# robot_sumo_easyeda.net
KiCad netlist of a schematic drawn in EasyEDA
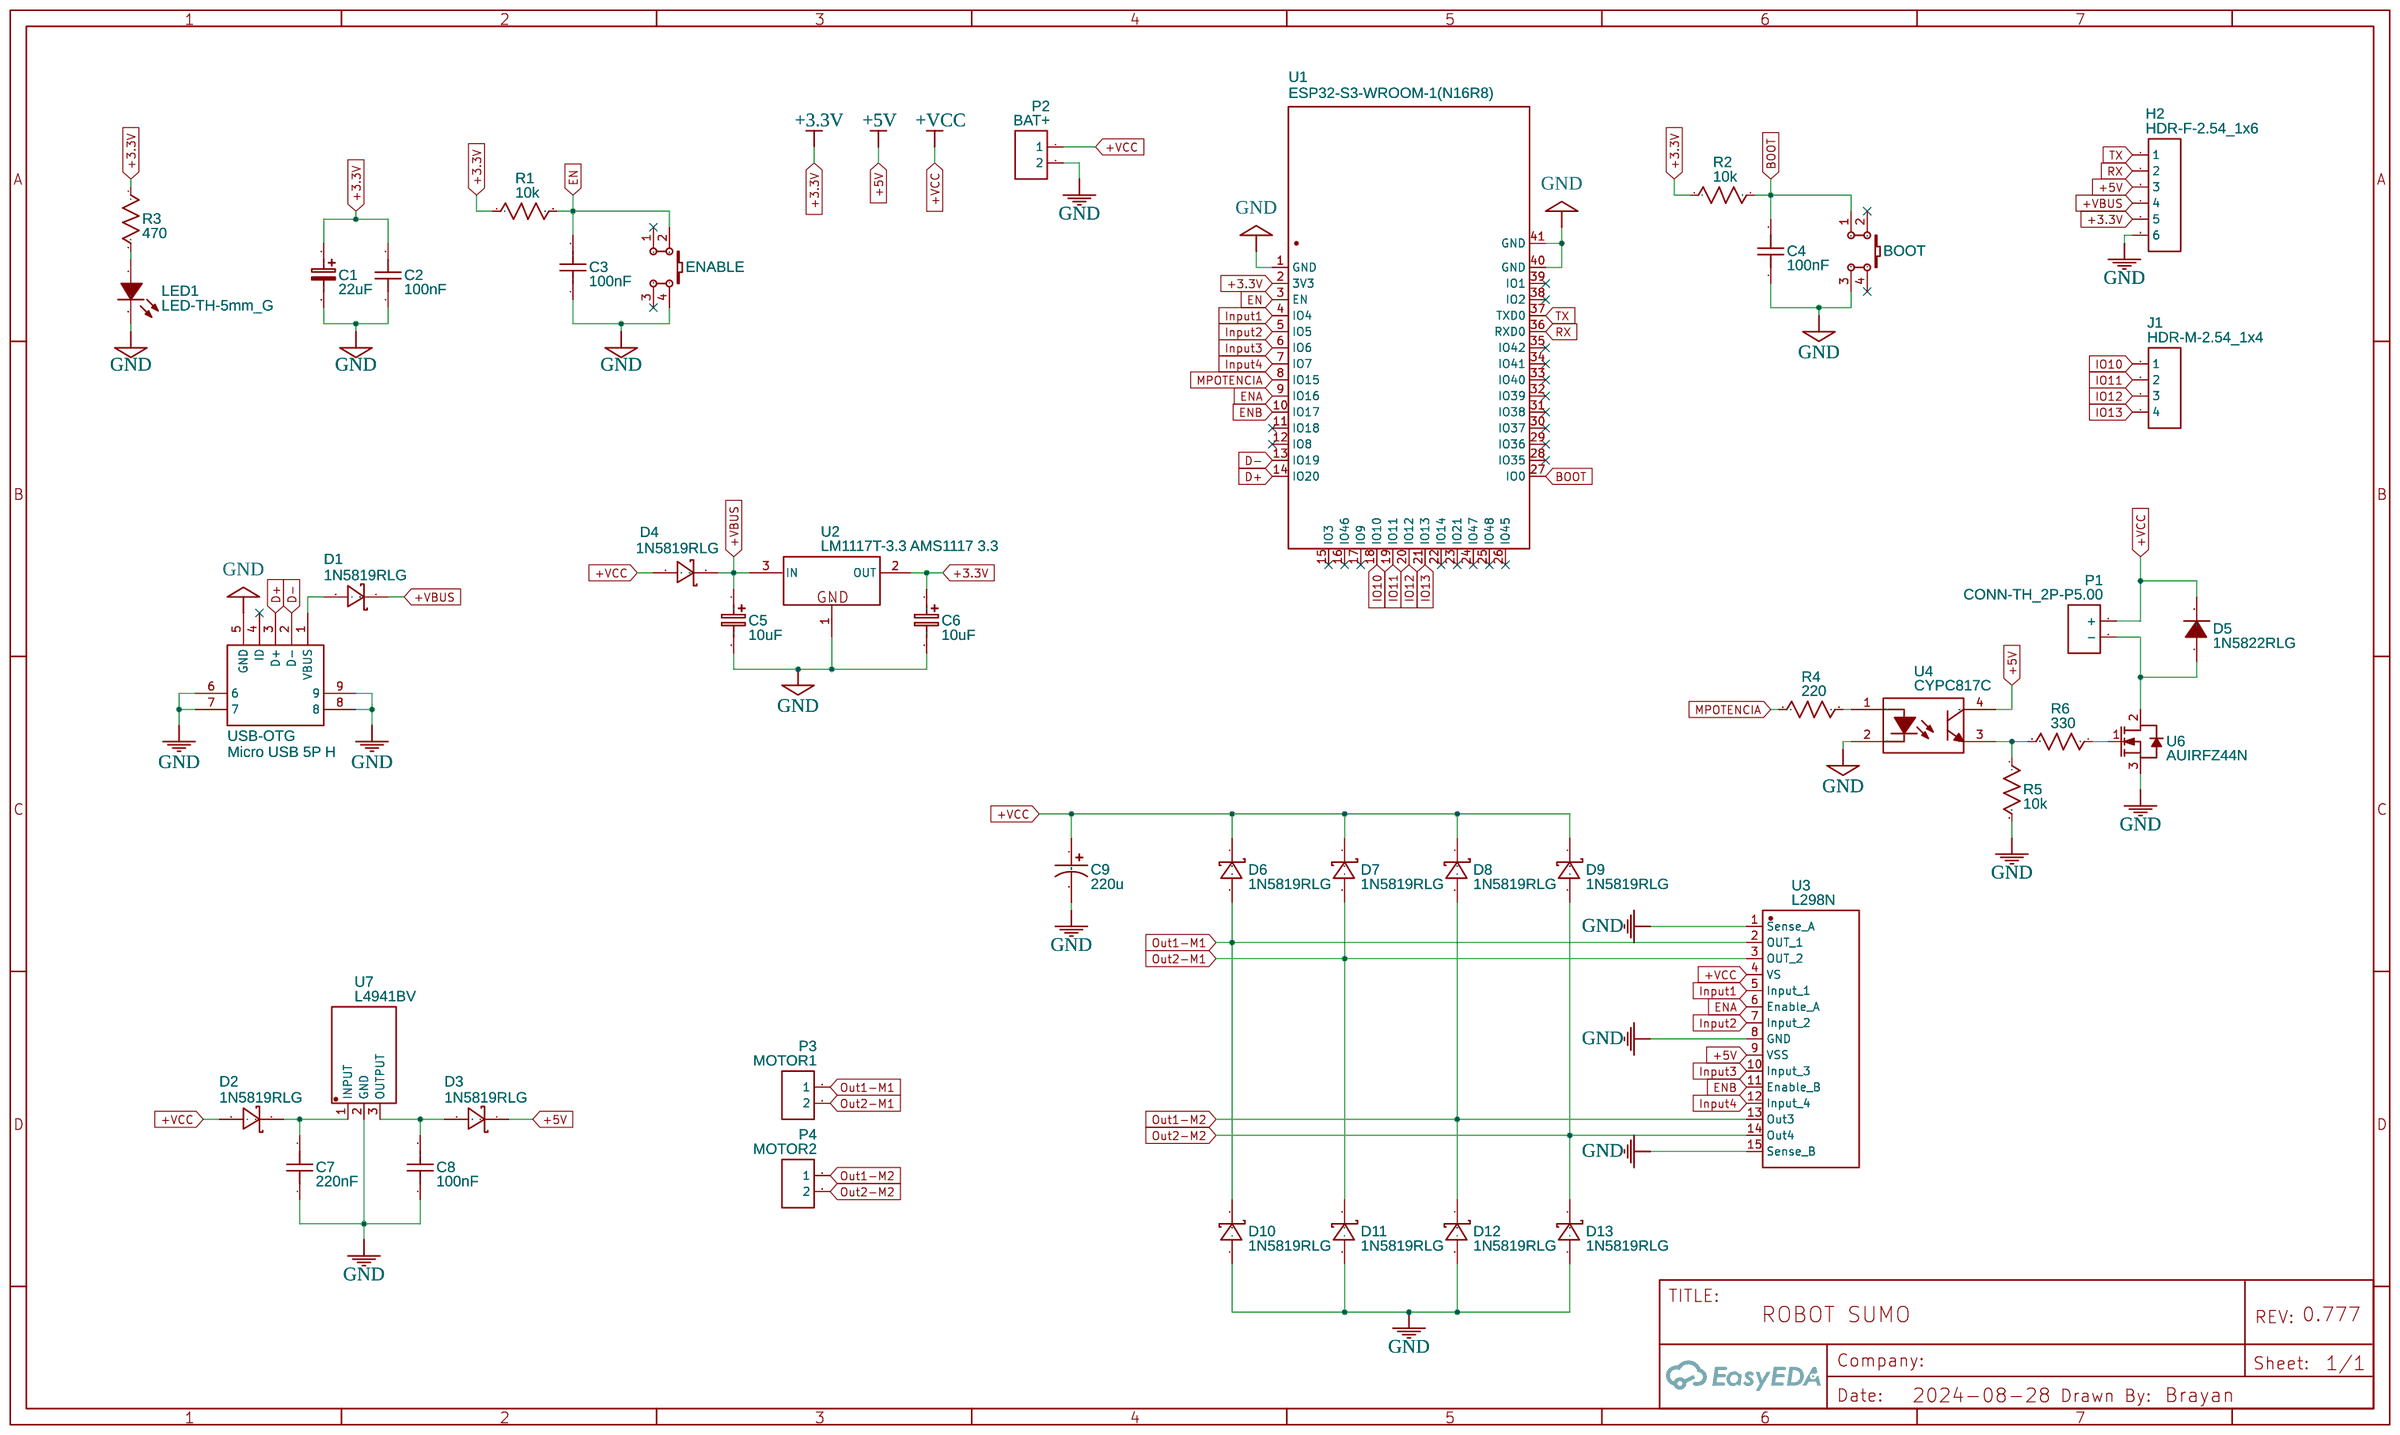
[diagram p0: schematic sheet]

(export (version "E")
  (design (tool "Eeschema 10.0.6"))
  (components
    (comp (ref "BOOT")
      (value "K4-6×6_TH")
      (fields (field (name "Manufacturer Part") "K2-1102DP-E4SW-04") (field (name "Manufacturer") "韩国韩荣"))
      (libsource (lib "") (part "K4-6×6_TH_1"))
    )
    (comp (ref "C1") (value "22uF") (libsource (lib "") (part "CE_TH_D5.0×F2.0_EU_2")))
    (comp (ref "C2")
      (value "100nF")
      (fields
        (field (name "Manufacturer Part") "CC1E104ZA1FD3F5O10MF")
        (field (name "Manufacturer") "Dersonic(德尔创)")
      )
      (libsource (lib "") (part "CC1E104ZA1FD3F5O10MF"))
    )
    (comp (ref "C3")
      (value "100nF")
      (fields
        (field (name "Manufacturer Part") "CC1E104ZA1FD3F5O10MF")
        (field (name "Manufacturer") "Dersonic(德尔创)")
      )
      (libsource (lib "") (part "CC1E104ZA1FD3F5O10MF"))
    )
    (comp (ref "C4")
      (value "100nF")
      (fields
        (field (name "Manufacturer Part") "CC1E104ZA1FD3F5O10MF")
        (field (name "Manufacturer") "Dersonic(德尔创)")
      )
      (libsource (lib "") (part "CC1E104ZA1FD3F5O10MF"))
    )
    (comp (ref "C5") (value "10uF") (libsource (lib "") (part "CE_TH_D5.0×F2.0_EU_1")))
    (comp (ref "C6") (value "10uF") (libsource (lib "") (part "CE_TH_D5.0×F2.0_EU")))
    (comp (ref "C7")
      (value "220nF")
      (fields
        (field (name "Manufacturer Part") "CC1E104ZA1FD3F5O10MF")
        (field (name "Manufacturer") "Dersonic(德尔创)")
      )
      (libsource (lib "") (part "CC1E104ZA1FD3F5O10MF"))
    )
    (comp (ref "C8")
      (value "100nF")
      (fields
        (field (name "Manufacturer Part") "CC1E104ZA1FD3F5O10MF")
        (field (name "Manufacturer") "Dersonic(德尔创)")
      )
      (libsource (lib "") (part "CC1E104ZA1FD3F5O10MF"))
    )
    (comp (ref "C9") (value "220u") (libsource (lib "") (part "CE_TH_D8.0×F3.5_US")))
    (comp (ref "D1")
      (value "1N5819RLG")
      (fields (field (name "Manufacturer") "onsemi(安森美)"))
      (libsource (lib "") (part "1N5819RLG_1"))
    )
    (comp (ref "D2")
      (value "1N5819RLG")
      (fields (field (name "Manufacturer") "onsemi(安森美)"))
      (libsource (lib "") (part "1N5819RLG_1"))
    )
    (comp (ref "D3")
      (value "1N5819RLG")
      (fields (field (name "Manufacturer") "onsemi(安森美)"))
      (libsource (lib "") (part "1N5819RLG_1"))
    )
    (comp (ref "D4")
      (value "1N5819RLG")
      (fields (field (name "Manufacturer") "onsemi(安森美)"))
      (libsource (lib "") (part "1N5819RLG_1"))
    )
    (comp (ref "D5")
      (value "1N5822RLG")
      (fields (field (name "Manufacturer") "onsemi(安森美)"))
      (libsource (lib "") (part "1N5822RLG"))
    )
    (comp (ref "D6")
      (value "1N5819RLG")
      (fields (field (name "Manufacturer") "onsemi(安森美)"))
      (libsource (lib "") (part "1N5819RLG"))
    )
    (comp (ref "D7")
      (value "1N5819RLG")
      (fields (field (name "Manufacturer") "onsemi(安森美)"))
      (libsource (lib "") (part "1N5819RLG"))
    )
    (comp (ref "D8")
      (value "1N5819RLG")
      (fields (field (name "Manufacturer") "onsemi(安森美)"))
      (libsource (lib "") (part "1N5819RLG"))
    )
    (comp (ref "D9")
      (value "1N5819RLG")
      (fields (field (name "Manufacturer") "onsemi(安森美)"))
      (libsource (lib "") (part "1N5819RLG"))
    )
    (comp (ref "D10")
      (value "1N5819RLG")
      (fields (field (name "Manufacturer") "onsemi(安森美)"))
      (libsource (lib "") (part "1N5819RLG"))
    )
    (comp (ref "D11")
      (value "1N5819RLG")
      (fields (field (name "Manufacturer") "onsemi(安森美)"))
      (libsource (lib "") (part "1N5819RLG"))
    )
    (comp (ref "D12")
      (value "1N5819RLG")
      (fields (field (name "Manufacturer") "onsemi(安森美)"))
      (libsource (lib "") (part "1N5819RLG"))
    )
    (comp (ref "D13")
      (value "1N5819RLG")
      (fields (field (name "Manufacturer") "onsemi(安森美)"))
      (libsource (lib "") (part "1N5819RLG"))
    )
    (comp (ref "ENABLE")
      (value "K4-6×6_TH")
      (fields (field (name "Manufacturer Part") "K2-1102DP-E4SW-04") (field (name "Manufacturer") "韩国韩荣"))
      (libsource (lib "") (part "K4-6×6_TH"))
    )
    (comp (ref "H2") (value "HDR-F-2.54_1x6") (libsource (lib "") (part "HDR-F-2.54_1x6")))
    (comp (ref "J1") (value "HDR-M-2.54_1x4") (libsource (lib "") (part "HDR-M-2.54_1x4")))
    (comp (ref "LED1")
      (value "LED-TH-5mm_G")
      (fields
        (field (name "Manufacturer Part") "333-2SYGD/S530-E2")
        (field (name "Manufacturer") "EVERLIGHT(台湾亿光)")
      )
      (libsource (lib "") (part "LED-TH-5mm_G"))
    )
    (comp (ref "P1") (value "CONN-TH_2P-P5.00") (libsource (lib "") (part "CONN-TH_2P-P5.00_1")))
    (comp (ref "P2") (value "BAT+") (libsource (lib "") (part "CONN-TH_2P-P5.00")))
    (comp (ref "P3") (value "MOTOR1") (libsource (lib "") (part "CONN-TH_2P-P5.00")))
    (comp (ref "P4") (value "MOTOR2") (libsource (lib "") (part "CONN-TH_2P-P5.00")))
    (comp (ref "R1") (value "10k") (libsource (lib "") (part "R_AXIAL-0.4_US")))
    (comp (ref "R2") (value "10k") (libsource (lib "") (part "R_AXIAL-0.4_US")))
    (comp (ref "R3") (value "470") (libsource (lib "") (part "R_AXIAL-0.4_US_2")))
    (comp (ref "R4") (value "220") (libsource (lib "") (part "R_AXIAL-0.4_US_1")))
    (comp (ref "R5") (value "10k") (libsource (lib "") (part "R_AXIAL-0.4_US_2")))
    (comp (ref "R6") (value "330") (libsource (lib "") (part "R_AXIAL-0.4_US_1")))
    (comp (ref "U1")
      (value "ESP32-S3-WROOM-1(N16R8)")
      (fields
        (field (name "Manufacturer Part") "ESP32-S3-WROOM-1-N16R8")
        (field (name "Manufacturer") "ESPRESSIF(乐鑫)")
      )
      (libsource (lib "") (part "ESP32-S3-WROOM-1(N16R8)"))
    )
    (comp (ref "U2")
      (value "LM1117T-3.3 AMS1117 3.3")
      (fields (field (name "Manufacturer Part") "LM1117T-3.3") (field (name "Manufacturer") "HGSEMI(华冠)"))
      (libsource (lib "") (part "LM1117T-3.3"))
    )
    (comp (ref "U3")
      (value "L298N")
      (fields (field (name "Manufacturer") "HGSEMI(华冠)"))
      (libsource (lib "") (part "L298N"))
    )
    (comp (ref "U4")
      (value "CYPC817C")
      (fields (field (name "Manufacturer") "OCIC(卓睿科)"))
      (libsource (lib "") (part "CYPC817C"))
    )
    (comp (ref "U6")
      (value "AUIRFZ44N")
      (fields (field (name "Manufacturer") "Infineon(英飞凌)"))
      (libsource (lib "") (part "AUIRFZ44N"))
    )
    (comp (ref "U7")
      (value "L4941BV")
      (fields (field (name "Manufacturer") "ST(意法半导体)"))
      (libsource (lib "") (part "L4941BV"))
    )
    (comp (ref "USB-OTG")
      (value "Micro USB 5P H")
      (fields (field (name "Manufacturer Part") "920-E52A2021S10101") (field (name "Manufacturer") "精拓金"))
      (libsource (lib "") (part "Micro USB 5P H"))
    )
  )
  (nets
    (net (code "1") (name "+3.3V") (class "Default")
      (node (ref "C1") (pin "1") (pinfunction "1_1") (pintype "unspecified"))
      (node (ref "C2") (pin "2") (pinfunction "2_2") (pintype "unspecified"))
      (node (ref "C6") (pin "1") (pinfunction "1_1") (pintype "unspecified"))
      (node (ref "H2") (pin "5") (pinfunction "5_5") (pintype "input"))
      (node (ref "R1") (pin "1") (pinfunction "1_1") (pintype "unspecified"))
      (node (ref "R2") (pin "1") (pinfunction "1_1") (pintype "unspecified"))
      (node (ref "R3") (pin "1") (pinfunction "1_1") (pintype "unspecified"))
      (node (ref "U1") (pin "2") (pinfunction "3V3_2") (pintype "unspecified"))
      (node (ref "U2") (pin "2") (pinfunction "OUT_2") (pintype "unspecified"))
    )
    (net (code "2") (name "+5V") (class "Default")
      (node (ref "D3") (pin "1") (pinfunction "C_1") (pintype "unspecified"))
      (node (ref "H2") (pin "3") (pinfunction "3_3") (pintype "input"))
      (node (ref "U3") (pin "9") (pinfunction "VSS_9") (pintype "unspecified"))
      (node (ref "U4") (pin "4") (pinfunction "COL_4") (pintype "unspecified"))
    )
    (net (code "3") (name "+VBUS") (class "Default")
      (node (ref "C5") (pin "1") (pinfunction "1_1") (pintype "unspecified"))
      (node (ref "D1") (pin "1") (pinfunction "C_1") (pintype "unspecified"))
      (node (ref "D4") (pin "1") (pinfunction "C_1") (pintype "unspecified"))
      (node (ref "H2") (pin "4") (pinfunction "4_4") (pintype "input"))
      (node (ref "U2") (pin "3") (pinfunction "IN_3") (pintype "unspecified"))
    )
    (net (code "4") (name "+VCC") (class "Default")
      (node (ref "C9") (pin "1") (pinfunction "1_1") (pintype "unspecified"))
      (node (ref "D2") (pin "2") (pinfunction "A_2") (pintype "unspecified"))
      (node (ref "D4") (pin "2") (pinfunction "A_2") (pintype "unspecified"))
      (node (ref "D5") (pin "1") (pinfunction "C_1") (pintype "unspecified"))
      (node (ref "D6") (pin "1") (pinfunction "C_1") (pintype "unspecified"))
      (node (ref "D7") (pin "1") (pinfunction "C_1") (pintype "unspecified"))
      (node (ref "D8") (pin "1") (pinfunction "C_1") (pintype "unspecified"))
      (node (ref "D9") (pin "1") (pinfunction "C_1") (pintype "unspecified"))
      (node (ref "P1") (pin "1") (pinfunction "+_1") (pintype "unspecified"))
      (node (ref "P2") (pin "1") (pinfunction "1_1") (pintype "unspecified"))
      (node (ref "U3") (pin "4") (pinfunction "VS_4") (pintype "unspecified"))
    )
    (net (code "5") (name "BOOT") (class "Default")
      (node (ref "BOOT") (pin "1") (pinfunction "1_1") (pintype "unspecified"))
      (node (ref "C4") (pin "2") (pinfunction "2_2") (pintype "unspecified"))
      (node (ref "R2") (pin "2") (pinfunction "2_2") (pintype "unspecified"))
      (node (ref "U1") (pin "27") (pinfunction "IO0_27") (pintype "unspecified"))
    )
    (net (code "6") (name "D+") (class "Default")
      (node (ref "U1") (pin "14") (pinfunction "IO20_14") (pintype "unspecified"))
      (node (ref "USB-OTG") (pin "3") (pinfunction "D+_3") (pintype "unspecified"))
    )
    (net (code "7") (name "D-") (class "Default")
      (node (ref "U1") (pin "13") (pinfunction "IO19_13") (pintype "unspecified"))
      (node (ref "USB-OTG") (pin "2") (pinfunction "D-_2") (pintype "unspecified"))
    )
    (net (code "8") (name "EN") (class "Default")
      (node (ref "C3") (pin "2") (pinfunction "2_2") (pintype "unspecified"))
      (node (ref "ENABLE") (pin "2") (pinfunction "2_2") (pintype "unspecified"))
      (node (ref "R1") (pin "2") (pinfunction "2_2") (pintype "unspecified"))
      (node (ref "U1") (pin "3") (pinfunction "EN_3") (pintype "unspecified"))
    )
    (net (code "9") (name "ENA") (class "Default")
      (node (ref "U1") (pin "9") (pinfunction "IO16_9") (pintype "unspecified"))
      (node (ref "U3") (pin "6") (pinfunction "Enable_A_6") (pintype "unspecified"))
    )
    (net (code "10") (name "ENB") (class "Default")
      (node (ref "U1") (pin "10") (pinfunction "IO17_10") (pintype "unspecified"))
      (node (ref "U3") (pin "11") (pinfunction "Enable_B_11") (pintype "unspecified"))
    )
    (net (code "11") (name "GND") (class "Default")
      (node (ref "BOOT") (pin "3") (pinfunction "3_3") (pintype "unspecified"))
      (node (ref "C1") (pin "2") (pinfunction "2_2") (pintype "unspecified"))
      (node (ref "C2") (pin "1") (pinfunction "1_1") (pintype "unspecified"))
      (node (ref "C3") (pin "1") (pinfunction "1_1") (pintype "unspecified"))
      (node (ref "C4") (pin "1") (pinfunction "1_1") (pintype "unspecified"))
      (node (ref "C5") (pin "2") (pinfunction "2_2") (pintype "unspecified"))
      (node (ref "C6") (pin "2") (pinfunction "2_2") (pintype "unspecified"))
      (node (ref "C7") (pin "1") (pinfunction "1_1") (pintype "unspecified"))
      (node (ref "C8") (pin "1") (pinfunction "1_1") (pintype "unspecified"))
      (node (ref "C9") (pin "2") (pinfunction "2_2") (pintype "unspecified"))
      (node (ref "D10") (pin "2") (pinfunction "A_2") (pintype "unspecified"))
      (node (ref "D11") (pin "2") (pinfunction "A_2") (pintype "unspecified"))
      (node (ref "D12") (pin "2") (pinfunction "A_2") (pintype "unspecified"))
      (node (ref "D13") (pin "2") (pinfunction "A_2") (pintype "unspecified"))
      (node (ref "ENABLE") (pin "4") (pinfunction "4_4") (pintype "unspecified"))
      (node (ref "H2") (pin "6") (pinfunction "6_6") (pintype "input"))
      (node (ref "LED1") (pin "2") (pinfunction "2_2") (pintype "unspecified"))
      (node (ref "P2") (pin "2") (pinfunction "2_2") (pintype "unspecified"))
      (node (ref "R5") (pin "2") (pinfunction "2_2") (pintype "unspecified"))
      (node (ref "U1") (pin "1") (pinfunction "GND_1") (pintype "unspecified"))
      (node (ref "U1") (pin "40") (pinfunction "GND_40") (pintype "unspecified"))
      (node (ref "U1") (pin "41") (pinfunction "GND_41") (pintype "unspecified"))
      (node (ref "U2") (pin "1") (pinfunction "GND_1") (pintype "unspecified"))
      (node (ref "U3") (pin "1") (pinfunction "Sense_A_1") (pintype "unspecified"))
      (node (ref "U3") (pin "15") (pinfunction "Sense_B_15") (pintype "unspecified"))
      (node (ref "U3") (pin "8") (pinfunction "GND_8") (pintype "unspecified"))
      (node (ref "U4") (pin "2") (pinfunction "CAT_2") (pintype "unspecified"))
      (node (ref "U6") (pin "3") (pinfunction "S_3") (pintype "unspecified"))
      (node (ref "U7") (pin "2") (pinfunction "GND_2") (pintype "unspecified"))
      (node (ref "USB-OTG") (pin "5") (pinfunction "GND_5") (pintype "unspecified"))
      (node (ref "USB-OTG") (pin "6") (pinfunction "6_6") (pintype "unspecified"))
      (node (ref "USB-OTG") (pin "7") (pinfunction "7_7") (pintype "unspecified"))
      (node (ref "USB-OTG") (pin "8") (pinfunction "8_8") (pintype "unspecified"))
      (node (ref "USB-OTG") (pin "9") (pinfunction "9_9") (pintype "unspecified"))
    )
    (net (code "12") (name "IO10") (class "Default")
      (node (ref "J1") (pin "1") (pinfunction "1_1") (pintype "unspecified"))
      (node (ref "U1") (pin "18") (pinfunction "IO10_18") (pintype "unspecified"))
    )
    (net (code "13") (name "IO11") (class "Default")
      (node (ref "J1") (pin "2") (pinfunction "2_2") (pintype "unspecified"))
      (node (ref "U1") (pin "19") (pinfunction "IO11_19") (pintype "unspecified"))
    )
    (net (code "14") (name "IO12") (class "Default")
      (node (ref "J1") (pin "3") (pinfunction "3_3") (pintype "unspecified"))
      (node (ref "U1") (pin "20") (pinfunction "IO12_20") (pintype "unspecified"))
    )
    (net (code "15") (name "IO13") (class "Default")
      (node (ref "J1") (pin "4") (pinfunction "4_4") (pintype "unspecified"))
      (node (ref "U1") (pin "21") (pinfunction "IO13_21") (pintype "unspecified"))
    )
    (net (code "16") (name "Input1") (class "Default")
      (node (ref "U1") (pin "4") (pinfunction "IO4_4") (pintype "unspecified"))
      (node (ref "U3") (pin "5") (pinfunction "Input_1_5") (pintype "unspecified"))
    )
    (net (code "17") (name "Input2") (class "Default")
      (node (ref "U1") (pin "5") (pinfunction "IO5_5") (pintype "unspecified"))
      (node (ref "U3") (pin "7") (pinfunction "Input_2_7") (pintype "unspecified"))
    )
    (net (code "18") (name "Input3") (class "Default")
      (node (ref "U1") (pin "6") (pinfunction "IO6_6") (pintype "unspecified"))
      (node (ref "U3") (pin "10") (pinfunction "Input_3_10") (pintype "unspecified"))
    )
    (net (code "19") (name "Input4") (class "Default")
      (node (ref "U1") (pin "7") (pinfunction "IO7_7") (pintype "unspecified"))
      (node (ref "U3") (pin "12") (pinfunction "Input_4_12") (pintype "unspecified"))
    )
    (net (code "20") (name "MPOTENCIA") (class "Default")
      (node (ref "R4") (pin "2") (pinfunction "2_2") (pintype "unspecified"))
      (node (ref "U1") (pin "8") (pinfunction "IO15_8") (pintype "unspecified"))
    )
    (net (code "21") (name "Net-(D1-A)") (class "Default")
      (node (ref "D1") (pin "2") (pinfunction "A_2") (pintype "unspecified"))
      (node (ref "USB-OTG") (pin "1") (pinfunction "VBUS_1") (pintype "unspecified"))
    )
    (net (code "22") (name "Net-(D2-C)") (class "Default")
      (node (ref "C7") (pin "2") (pinfunction "2_2") (pintype "unspecified"))
      (node (ref "D2") (pin "1") (pinfunction "C_1") (pintype "unspecified"))
      (node (ref "U7") (pin "1") (pinfunction "INPUT_1") (pintype "unspecified"))
    )
    (net (code "23") (name "Net-(D3-A)") (class "Default")
      (node (ref "C8") (pin "2") (pinfunction "2_2") (pintype "unspecified"))
      (node (ref "D3") (pin "2") (pinfunction "A_2") (pintype "unspecified"))
      (node (ref "U7") (pin "3") (pinfunction "OUTPUT_3") (pintype "unspecified"))
    )
    (net (code "24") (name "Net-(D5-A)") (class "Default")
      (node (ref "D5") (pin "2") (pinfunction "A_2") (pintype "unspecified"))
      (node (ref "P1") (pin "2") (pinfunction "-_2") (pintype "unspecified"))
      (node (ref "U6") (pin "2") (pinfunction "D_2") (pintype "unspecified"))
    )
    (net (code "25") (name "Net-(LED1-Pad1)") (class "Default")
      (node (ref "LED1") (pin "1") (pinfunction "1_1") (pintype "unspecified"))
      (node (ref "R3") (pin "2") (pinfunction "2_2") (pintype "unspecified"))
    )
    (net (code "26") (name "Net-(U4-AN)") (class "Default")
      (node (ref "R4") (pin "1") (pinfunction "1_1") (pintype "unspecified"))
      (node (ref "U4") (pin "1") (pinfunction "AN_1") (pintype "unspecified"))
    )
    (net (code "27") (name "Net-(U4-EMI)") (class "Default")
      (node (ref "R5") (pin "1") (pinfunction "1_1") (pintype "unspecified"))
      (node (ref "R6") (pin "2") (pinfunction "2_2") (pintype "unspecified"))
      (node (ref "U4") (pin "3") (pinfunction "EMI_3") (pintype "unspecified"))
    )
    (net (code "28") (name "Net-(U6-G)") (class "Default")
      (node (ref "R6") (pin "1") (pinfunction "1_1") (pintype "unspecified"))
      (node (ref "U6") (pin "1") (pinfunction "G_1") (pintype "unspecified"))
    )
    (net (code "29") (name "Out1-M1") (class "Default")
      (node (ref "D10") (pin "1") (pinfunction "C_1") (pintype "unspecified"))
      (node (ref "D6") (pin "2") (pinfunction "A_2") (pintype "unspecified"))
      (node (ref "P3") (pin "1") (pinfunction "1_1") (pintype "unspecified"))
      (node (ref "U3") (pin "2") (pinfunction "OUT_1_2") (pintype "unspecified"))
    )
    (net (code "30") (name "Out1-M2") (class "Default")
      (node (ref "D12") (pin "1") (pinfunction "C_1") (pintype "unspecified"))
      (node (ref "D8") (pin "2") (pinfunction "A_2") (pintype "unspecified"))
      (node (ref "P4") (pin "1") (pinfunction "1_1") (pintype "unspecified"))
      (node (ref "U3") (pin "13") (pinfunction "Out3_13") (pintype "unspecified"))
    )
    (net (code "31") (name "Out2-M1") (class "Default")
      (node (ref "D11") (pin "1") (pinfunction "C_1") (pintype "unspecified"))
      (node (ref "D7") (pin "2") (pinfunction "A_2") (pintype "unspecified"))
      (node (ref "P3") (pin "2") (pinfunction "2_2") (pintype "unspecified"))
      (node (ref "U3") (pin "3") (pinfunction "OUT_2_3") (pintype "unspecified"))
    )
    (net (code "32") (name "Out2-M2") (class "Default")
      (node (ref "D13") (pin "1") (pinfunction "C_1") (pintype "unspecified"))
      (node (ref "D9") (pin "2") (pinfunction "A_2") (pintype "unspecified"))
      (node (ref "P4") (pin "2") (pinfunction "2_2") (pintype "unspecified"))
      (node (ref "U3") (pin "14") (pinfunction "Out4_14") (pintype "unspecified"))
    )
    (net (code "33") (name "RX") (class "Default")
      (node (ref "H2") (pin "2") (pinfunction "2_2") (pintype "input"))
      (node (ref "U1") (pin "36") (pinfunction "RXD0_36") (pintype "unspecified"))
    )
    (net (code "34") (name "TX") (class "Default")
      (node (ref "H2") (pin "1") (pinfunction "1_1") (pintype "input"))
      (node (ref "U1") (pin "37") (pinfunction "TXD0_37") (pintype "unspecified"))
    )
    (net (code "35") (name "unconnected-(BOOT-Pad2)") (class "Default")
      (node (ref "BOOT") (pin "2") (pinfunction "2_2") (pintype "unspecified+no_connect"))
    )
    (net (code "36") (name "unconnected-(BOOT-Pad4)") (class "Default")
      (node (ref "BOOT") (pin "4") (pinfunction "4_4") (pintype "unspecified+no_connect"))
    )
    (net (code "37") (name "unconnected-(ENABLE-Pad1)") (class "Default")
      (node (ref "ENABLE") (pin "1") (pinfunction "1_1") (pintype "unspecified+no_connect"))
    )
    (net (code "38") (name "unconnected-(ENABLE-Pad3)") (class "Default")
      (node (ref "ENABLE") (pin "3") (pinfunction "3_3") (pintype "unspecified+no_connect"))
    )
    (net (code "39") (name "unconnected-(U1-IO1-Pad39)") (class "Default")
      (node (ref "U1") (pin "39") (pinfunction "IO1_39") (pintype "unspecified+no_connect"))
    )
    (net (code "40") (name "unconnected-(U1-IO2-Pad38)") (class "Default")
      (node (ref "U1") (pin "38") (pinfunction "IO2_38") (pintype "unspecified+no_connect"))
    )
    (net (code "41") (name "unconnected-(U1-IO3-Pad15)") (class "Default")
      (node (ref "U1") (pin "15") (pinfunction "IO3_15") (pintype "unspecified+no_connect"))
    )
    (net (code "42") (name "unconnected-(U1-IO8-Pad12)") (class "Default")
      (node (ref "U1") (pin "12") (pinfunction "IO8_12") (pintype "unspecified+no_connect"))
    )
    (net (code "43") (name "unconnected-(U1-IO9-Pad17)") (class "Default")
      (node (ref "U1") (pin "17") (pinfunction "IO9_17") (pintype "unspecified+no_connect"))
    )
    (net (code "44") (name "unconnected-(U1-IO14-Pad22)") (class "Default")
      (node (ref "U1") (pin "22") (pinfunction "IO14_22") (pintype "unspecified+no_connect"))
    )
    (net (code "45") (name "unconnected-(U1-IO18-Pad11)") (class "Default")
      (node (ref "U1") (pin "11") (pinfunction "IO18_11") (pintype "unspecified+no_connect"))
    )
    (net (code "46") (name "unconnected-(U1-IO21-Pad23)") (class "Default")
      (node (ref "U1") (pin "23") (pinfunction "IO21_23") (pintype "unspecified+no_connect"))
    )
    (net (code "47") (name "unconnected-(U1-IO35-Pad28)") (class "Default")
      (node (ref "U1") (pin "28") (pinfunction "IO35_28") (pintype "unspecified+no_connect"))
    )
    (net (code "48") (name "unconnected-(U1-IO36-Pad29)") (class "Default")
      (node (ref "U1") (pin "29") (pinfunction "IO36_29") (pintype "unspecified+no_connect"))
    )
    (net (code "49") (name "unconnected-(U1-IO37-Pad30)") (class "Default")
      (node (ref "U1") (pin "30") (pinfunction "IO37_30") (pintype "unspecified+no_connect"))
    )
    (net (code "50") (name "unconnected-(U1-IO38-Pad31)") (class "Default")
      (node (ref "U1") (pin "31") (pinfunction "IO38_31") (pintype "unspecified+no_connect"))
    )
    (net (code "51") (name "unconnected-(U1-IO39-Pad32)") (class "Default")
      (node (ref "U1") (pin "32") (pinfunction "IO39_32") (pintype "unspecified+no_connect"))
    )
    (net (code "52") (name "unconnected-(U1-IO40-Pad33)") (class "Default")
      (node (ref "U1") (pin "33") (pinfunction "IO40_33") (pintype "unspecified+no_connect"))
    )
    (net (code "53") (name "unconnected-(U1-IO41-Pad34)") (class "Default")
      (node (ref "U1") (pin "34") (pinfunction "IO41_34") (pintype "unspecified+no_connect"))
    )
    (net (code "54") (name "unconnected-(U1-IO42-Pad35)") (class "Default")
      (node (ref "U1") (pin "35") (pinfunction "IO42_35") (pintype "unspecified+no_connect"))
    )
    (net (code "55") (name "unconnected-(U1-IO45-Pad26)") (class "Default")
      (node (ref "U1") (pin "26") (pinfunction "IO45_26") (pintype "unspecified+no_connect"))
    )
    (net (code "56") (name "unconnected-(U1-IO46-Pad16)") (class "Default")
      (node (ref "U1") (pin "16") (pinfunction "IO46_16") (pintype "unspecified+no_connect"))
    )
    (net (code "57") (name "unconnected-(U1-IO47-Pad24)") (class "Default")
      (node (ref "U1") (pin "24") (pinfunction "IO47_24") (pintype "unspecified+no_connect"))
    )
    (net (code "58") (name "unconnected-(U1-IO48-Pad25)") (class "Default")
      (node (ref "U1") (pin "25") (pinfunction "IO48_25") (pintype "unspecified+no_connect"))
    )
    (net (code "59") (name "unconnected-(USB-OTG-ID-Pad4)") (class "Default")
      (node (ref "USB-OTG") (pin "4") (pinfunction "ID_4") (pintype "unspecified+no_connect"))
    )
  )
)
